# io_bottom.net
KiCad netlist of a schematic drawn in EAGLE
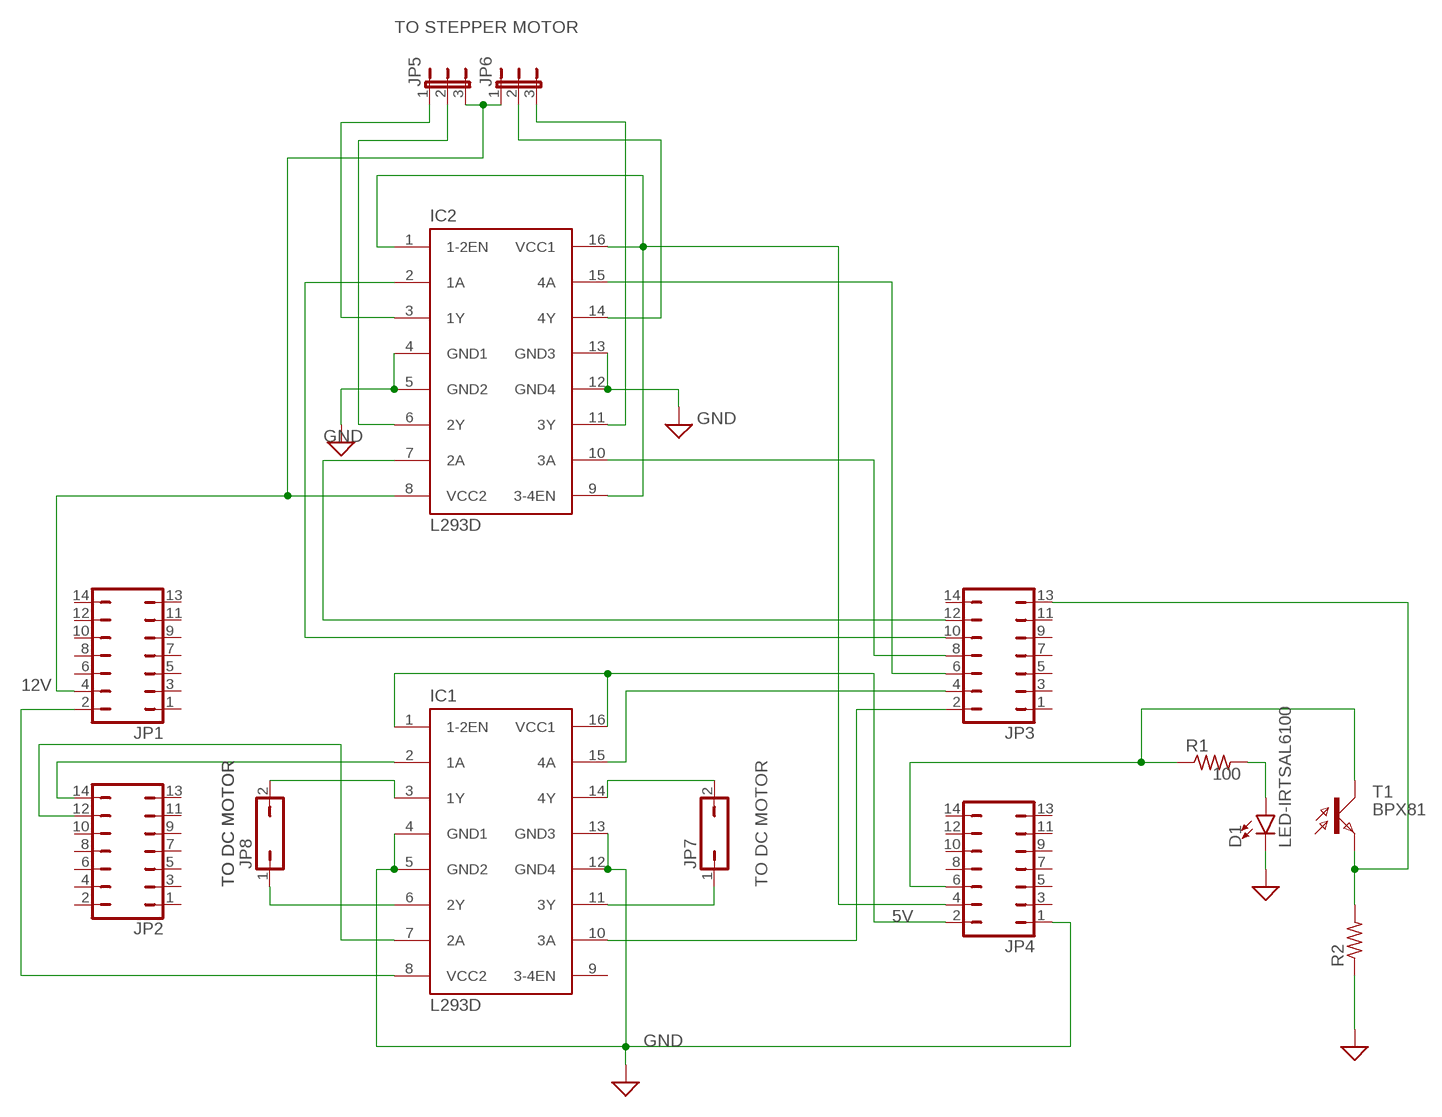
[diagram p0: schematic, sheet 1]

(export (version "E")
  (design (tool "Eeschema 10.0.6"))
  (components
    (comp (ref "D1")
      (value "LED-IRTSAL6100")
      (footprint "eagle-import:LED_5MM")
      (libsource (lib "eagle-import") (part "LED-IRTSAL6100"))
    )
    (comp (ref "IC1")
      (value "L293D")
      (footprint "eagle-import:DIL16")
      (libsource (lib "eagle-import") (part "L293D"))
    )
    (comp (ref "IC2")
      (value "L293D")
      (footprint "eagle-import:DIL16")
      (libsource (lib "eagle-import") (part "L293D"))
    )
    (comp (ref "JP1")
      (value "JP7Q")
      (footprint "eagle-import:JP7Q")
      (libsource (lib "eagle-import") (part "JP7Q"))
    )
    (comp (ref "JP2")
      (value "JP7Q")
      (footprint "eagle-import:JP7Q")
      (libsource (lib "eagle-import") (part "JP7Q"))
    )
    (comp (ref "JP3")
      (value "JP7Q")
      (footprint "eagle-import:JP7Q")
      (libsource (lib "eagle-import") (part "JP7Q"))
    )
    (comp (ref "JP4")
      (value "JP7Q")
      (footprint "eagle-import:JP7Q")
      (libsource (lib "eagle-import") (part "JP7Q"))
    )
    (comp (ref "JP5")
      (value "JP2E")
      (footprint "eagle-import:JP2")
      (libsource (lib "eagle-import") (part "JP2E"))
    )
    (comp (ref "JP6")
      (value "JP2E")
      (footprint "eagle-import:JP2")
      (libsource (lib "eagle-import") (part "JP2E"))
    )
    (comp (ref "JP7")
      (value "JP1Q")
      (footprint "eagle-import:JP1")
      (libsource (lib "eagle-import") (part "JP1Q"))
    )
    (comp (ref "JP8")
      (value "JP1Q")
      (footprint "eagle-import:JP1")
      (libsource (lib "eagle-import") (part "JP1Q"))
    )
    (comp (ref "R1")
      (value "R-US_0204/2V")
      (footprint "eagle-import:0204V")
      (libsource (lib "eagle-import") (part "R-US_0204/2V"))
    )
    (comp (ref "R2")
      (value "R-US_0204/2V")
      (footprint "eagle-import:0204V")
      (libsource (lib "eagle-import") (part "R-US_0204/2V"))
    )
    (comp (ref "T1")
      (value "BPX81")
      (footprint "eagle-import:BPX81")
      (libsource (lib "eagle-import") (part "BPX81"))
    )
  )
  (nets
    (net (code "1") (name "/5V") (class "Default")
      (node (ref "IC1") (pin "8") (pinfunction "VCC2_8") (pintype "power_in"))
      (node (ref "JP1") (pin "2") (pinfunction "2_2") (pintype "passive"))
    )
    (net (code "2") (name "Net-(D1-PadA)") (class "Default")
      (node (ref "D1") (pin "A") (pinfunction "A_A") (pintype "passive"))
      (node (ref "R1") (pin "2") (pinfunction "2_2") (pintype "passive"))
    )
    (net (code "3") (name "Net-(IC1-1-2EN)") (class "Default")
      (node (ref "IC1") (pin "1") (pinfunction "1-2EN_1") (pintype "input"))
      (node (ref "IC1") (pin "16") (pinfunction "VCC1_16") (pintype "power_in"))
      (node (ref "JP4") (pin "2") (pinfunction "2_2") (pintype "passive"))
    )
    (net (code "4") (name "Net-(IC1-1A)") (class "Default")
      (node (ref "IC1") (pin "2") (pinfunction "1A_2") (pintype "input"))
      (node (ref "JP2") (pin "14") (pinfunction "14_14") (pintype "passive"))
    )
    (net (code "5") (name "Net-(IC1-1Y)") (class "Default")
      (node (ref "IC1") (pin "3") (pinfunction "1Y_3") (pintype "output"))
      (node (ref "JP8") (pin "2") (pinfunction "2_2") (pintype "passive"))
    )
    (net (code "6") (name "Net-(IC1-2A)") (class "Default")
      (node (ref "IC1") (pin "7") (pinfunction "2A_7") (pintype "input"))
      (node (ref "JP2") (pin "12") (pinfunction "12_12") (pintype "passive"))
    )
    (net (code "7") (name "Net-(IC1-2Y)") (class "Default")
      (node (ref "IC1") (pin "6") (pinfunction "2Y_6") (pintype "output"))
      (node (ref "JP8") (pin "1") (pinfunction "1_1") (pintype "passive"))
    )
    (net (code "8") (name "Net-(IC1-3A)") (class "Default")
      (node (ref "IC1") (pin "10") (pinfunction "3A_10") (pintype "input"))
      (node (ref "JP3") (pin "2") (pinfunction "2_2") (pintype "passive"))
    )
    (net (code "9") (name "Net-(IC1-3Y)") (class "Default")
      (node (ref "IC1") (pin "11") (pinfunction "3Y_11") (pintype "output"))
      (node (ref "JP7") (pin "1") (pinfunction "1_1") (pintype "passive"))
    )
    (net (code "10") (name "Net-(IC1-4A)") (class "Default")
      (node (ref "IC1") (pin "15") (pinfunction "4A_15") (pintype "input"))
      (node (ref "JP3") (pin "4") (pinfunction "4_4") (pintype "passive"))
    )
    (net (code "11") (name "Net-(IC1-4Y)") (class "Default")
      (node (ref "IC1") (pin "14") (pinfunction "4Y_14") (pintype "output"))
      (node (ref "JP7") (pin "2") (pinfunction "2_2") (pintype "passive"))
    )
    (net (code "12") (name "Net-(IC2-1-2EN)") (class "Default")
      (node (ref "IC2") (pin "1") (pinfunction "1-2EN_1") (pintype "input"))
      (node (ref "IC2") (pin "16") (pinfunction "VCC1_16") (pintype "power_in"))
      (node (ref "IC2") (pin "9") (pinfunction "3-4EN_9") (pintype "input"))
      (node (ref "JP4") (pin "4") (pinfunction "4_4") (pintype "passive"))
    )
    (net (code "13") (name "Net-(IC2-1A)") (class "Default")
      (node (ref "IC2") (pin "2") (pinfunction "1A_2") (pintype "input"))
      (node (ref "JP3") (pin "10") (pinfunction "10_10") (pintype "passive"))
    )
    (net (code "14") (name "Net-(IC2-1Y)") (class "Default")
      (node (ref "IC2") (pin "3") (pinfunction "1Y_3") (pintype "output"))
      (node (ref "JP5") (pin "1") (pinfunction "1_1") (pintype "passive"))
    )
    (net (code "15") (name "Net-(IC2-2A)") (class "Default")
      (node (ref "IC2") (pin "7") (pinfunction "2A_7") (pintype "input"))
      (node (ref "JP3") (pin "12") (pinfunction "12_12") (pintype "passive"))
    )
    (net (code "16") (name "Net-(IC2-2Y)") (class "Default")
      (node (ref "IC2") (pin "6") (pinfunction "2Y_6") (pintype "output"))
      (node (ref "JP5") (pin "2") (pinfunction "2_2") (pintype "passive"))
    )
    (net (code "17") (name "Net-(IC2-3A)") (class "Default")
      (node (ref "IC2") (pin "10") (pinfunction "3A_10") (pintype "input"))
      (node (ref "JP3") (pin "8") (pinfunction "8_8") (pintype "passive"))
    )
    (net (code "18") (name "Net-(IC2-3Y)") (class "Default")
      (node (ref "IC2") (pin "11") (pinfunction "3Y_11") (pintype "output"))
      (node (ref "JP6") (pin "3") (pinfunction "3_3") (pintype "passive"))
    )
    (net (code "19") (name "Net-(IC2-4A)") (class "Default")
      (node (ref "IC2") (pin "15") (pinfunction "4A_15") (pintype "input"))
      (node (ref "JP3") (pin "6") (pinfunction "6_6") (pintype "passive"))
    )
    (net (code "20") (name "Net-(IC2-4Y)") (class "Default")
      (node (ref "IC2") (pin "14") (pinfunction "4Y_14") (pintype "output"))
      (node (ref "JP6") (pin "2") (pinfunction "2_2") (pintype "passive"))
    )
    (net (code "21") (name "Net-(IC2-VCC2)") (class "Default")
      (node (ref "IC2") (pin "8") (pinfunction "VCC2_8") (pintype "power_in"))
      (node (ref "JP1") (pin "4") (pinfunction "4_4") (pintype "passive"))
      (node (ref "JP5") (pin "3") (pinfunction "3_3") (pintype "passive"))
      (node (ref "JP6") (pin "1") (pinfunction "1_1") (pintype "passive"))
    )
    (net (code "22") (name "Net-(JP3-Pad13)") (class "Default")
      (node (ref "JP3") (pin "13") (pinfunction "13_13") (pintype "passive"))
      (node (ref "R2") (pin "2") (pinfunction "2_2") (pintype "passive"))
      (node (ref "T1") (pin "E") (pinfunction "E_E") (pintype "passive"))
    )
    (net (code "23") (name "Net-(JP4-Pad6)") (class "Default")
      (node (ref "JP4") (pin "6") (pinfunction "6_6") (pintype "passive"))
      (node (ref "R1") (pin "1") (pinfunction "1_1") (pintype "passive"))
      (node (ref "T1") (pin "C") (pinfunction "C_C") (pintype "passive"))
    )
    (net (code "24") (name "SUP") (class "Default")
      (node (ref "D1") (pin "K") (pinfunction "C_K") (pintype "passive"))
      (node (ref "IC1") (pin "12") (pinfunction "GND4_12") (pintype "power_in"))
      (node (ref "IC1") (pin "13") (pinfunction "GND3_13") (pintype "power_in"))
      (node (ref "IC1") (pin "4") (pinfunction "GND1_4") (pintype "power_in"))
      (node (ref "IC1") (pin "5") (pinfunction "GND2_5") (pintype "power_in"))
      (node (ref "IC2") (pin "12") (pinfunction "GND4_12") (pintype "power_in"))
      (node (ref "IC2") (pin "13") (pinfunction "GND3_13") (pintype "power_in"))
      (node (ref "IC2") (pin "4") (pinfunction "GND1_4") (pintype "power_in"))
      (node (ref "IC2") (pin "5") (pinfunction "GND2_5") (pintype "power_in"))
      (node (ref "JP4") (pin "1") (pinfunction "1_1") (pintype "passive"))
      (node (ref "R2") (pin "1") (pinfunction "1_1") (pintype "passive"))
    )
    (net (code "25") (name "unconnected-(IC1-3-4EN-Pad9)") (class "Default")
      (node (ref "IC1") (pin "9") (pinfunction "3-4EN_9") (pintype "input"))
    )
    (net (code "26") (name "unconnected-(JP1-Pad1)") (class "Default")
      (node (ref "JP1") (pin "1") (pinfunction "1_1") (pintype "passive"))
    )
    (net (code "27") (name "unconnected-(JP1-Pad3)") (class "Default")
      (node (ref "JP1") (pin "3") (pinfunction "3_3") (pintype "passive"))
    )
    (net (code "28") (name "unconnected-(JP1-Pad5)") (class "Default")
      (node (ref "JP1") (pin "5") (pinfunction "5_5") (pintype "passive"))
    )
    (net (code "29") (name "unconnected-(JP1-Pad6)") (class "Default")
      (node (ref "JP1") (pin "6") (pinfunction "6_6") (pintype "passive"))
    )
    (net (code "30") (name "unconnected-(JP1-Pad7)") (class "Default")
      (node (ref "JP1") (pin "7") (pinfunction "7_7") (pintype "passive"))
    )
    (net (code "31") (name "unconnected-(JP1-Pad8)") (class "Default")
      (node (ref "JP1") (pin "8") (pinfunction "8_8") (pintype "passive"))
    )
    (net (code "32") (name "unconnected-(JP1-Pad9)") (class "Default")
      (node (ref "JP1") (pin "9") (pinfunction "9_9") (pintype "passive"))
    )
    (net (code "33") (name "unconnected-(JP1-Pad10)") (class "Default")
      (node (ref "JP1") (pin "10") (pinfunction "10_10") (pintype "passive"))
    )
    (net (code "34") (name "unconnected-(JP1-Pad11)") (class "Default")
      (node (ref "JP1") (pin "11") (pinfunction "11_11") (pintype "passive"))
    )
    (net (code "35") (name "unconnected-(JP1-Pad12)") (class "Default")
      (node (ref "JP1") (pin "12") (pinfunction "12_12") (pintype "passive"))
    )
    (net (code "36") (name "unconnected-(JP1-Pad13)") (class "Default")
      (node (ref "JP1") (pin "13") (pinfunction "13_13") (pintype "passive"))
    )
    (net (code "37") (name "unconnected-(JP1-Pad14)") (class "Default")
      (node (ref "JP1") (pin "14") (pinfunction "14_14") (pintype "passive"))
    )
    (net (code "38") (name "unconnected-(JP2-Pad1)") (class "Default")
      (node (ref "JP2") (pin "1") (pinfunction "1_1") (pintype "passive"))
    )
    (net (code "39") (name "unconnected-(JP2-Pad2)") (class "Default")
      (node (ref "JP2") (pin "2") (pinfunction "2_2") (pintype "passive"))
    )
    (net (code "40") (name "unconnected-(JP2-Pad3)") (class "Default")
      (node (ref "JP2") (pin "3") (pinfunction "3_3") (pintype "passive"))
    )
    (net (code "41") (name "unconnected-(JP2-Pad4)") (class "Default")
      (node (ref "JP2") (pin "4") (pinfunction "4_4") (pintype "passive"))
    )
    (net (code "42") (name "unconnected-(JP2-Pad5)") (class "Default")
      (node (ref "JP2") (pin "5") (pinfunction "5_5") (pintype "passive"))
    )
    (net (code "43") (name "unconnected-(JP2-Pad6)") (class "Default")
      (node (ref "JP2") (pin "6") (pinfunction "6_6") (pintype "passive"))
    )
    (net (code "44") (name "unconnected-(JP2-Pad7)") (class "Default")
      (node (ref "JP2") (pin "7") (pinfunction "7_7") (pintype "passive"))
    )
    (net (code "45") (name "unconnected-(JP2-Pad8)") (class "Default")
      (node (ref "JP2") (pin "8") (pinfunction "8_8") (pintype "passive"))
    )
    (net (code "46") (name "unconnected-(JP2-Pad9)") (class "Default")
      (node (ref "JP2") (pin "9") (pinfunction "9_9") (pintype "passive"))
    )
    (net (code "47") (name "unconnected-(JP2-Pad10)") (class "Default")
      (node (ref "JP2") (pin "10") (pinfunction "10_10") (pintype "passive"))
    )
    (net (code "48") (name "unconnected-(JP2-Pad11)") (class "Default")
      (node (ref "JP2") (pin "11") (pinfunction "11_11") (pintype "passive"))
    )
    (net (code "49") (name "unconnected-(JP2-Pad13)") (class "Default")
      (node (ref "JP2") (pin "13") (pinfunction "13_13") (pintype "passive"))
    )
    (net (code "50") (name "unconnected-(JP3-Pad1)") (class "Default")
      (node (ref "JP3") (pin "1") (pinfunction "1_1") (pintype "passive"))
    )
    (net (code "51") (name "unconnected-(JP3-Pad3)") (class "Default")
      (node (ref "JP3") (pin "3") (pinfunction "3_3") (pintype "passive"))
    )
    (net (code "52") (name "unconnected-(JP3-Pad5)") (class "Default")
      (node (ref "JP3") (pin "5") (pinfunction "5_5") (pintype "passive"))
    )
    (net (code "53") (name "unconnected-(JP3-Pad7)") (class "Default")
      (node (ref "JP3") (pin "7") (pinfunction "7_7") (pintype "passive"))
    )
    (net (code "54") (name "unconnected-(JP3-Pad9)") (class "Default")
      (node (ref "JP3") (pin "9") (pinfunction "9_9") (pintype "passive"))
    )
    (net (code "55") (name "unconnected-(JP3-Pad11)") (class "Default")
      (node (ref "JP3") (pin "11") (pinfunction "11_11") (pintype "passive"))
    )
    (net (code "56") (name "unconnected-(JP3-Pad14)") (class "Default")
      (node (ref "JP3") (pin "14") (pinfunction "14_14") (pintype "passive"))
    )
    (net (code "57") (name "unconnected-(JP4-Pad3)") (class "Default")
      (node (ref "JP4") (pin "3") (pinfunction "3_3") (pintype "passive"))
    )
    (net (code "58") (name "unconnected-(JP4-Pad5)") (class "Default")
      (node (ref "JP4") (pin "5") (pinfunction "5_5") (pintype "passive"))
    )
    (net (code "59") (name "unconnected-(JP4-Pad7)") (class "Default")
      (node (ref "JP4") (pin "7") (pinfunction "7_7") (pintype "passive"))
    )
    (net (code "60") (name "unconnected-(JP4-Pad8)") (class "Default")
      (node (ref "JP4") (pin "8") (pinfunction "8_8") (pintype "passive"))
    )
    (net (code "61") (name "unconnected-(JP4-Pad9)") (class "Default")
      (node (ref "JP4") (pin "9") (pinfunction "9_9") (pintype "passive"))
    )
    (net (code "62") (name "unconnected-(JP4-Pad10)") (class "Default")
      (node (ref "JP4") (pin "10") (pinfunction "10_10") (pintype "passive"))
    )
    (net (code "63") (name "unconnected-(JP4-Pad11)") (class "Default")
      (node (ref "JP4") (pin "11") (pinfunction "11_11") (pintype "passive"))
    )
    (net (code "64") (name "unconnected-(JP4-Pad12)") (class "Default")
      (node (ref "JP4") (pin "12") (pinfunction "12_12") (pintype "passive"))
    )
    (net (code "65") (name "unconnected-(JP4-Pad13)") (class "Default")
      (node (ref "JP4") (pin "13") (pinfunction "13_13") (pintype "passive"))
    )
    (net (code "66") (name "unconnected-(JP4-Pad14)") (class "Default")
      (node (ref "JP4") (pin "14") (pinfunction "14_14") (pintype "passive"))
    )
  )
)
